# MCORD_AFE.net
KiCad netlist of a schematic drawn in Altium Designer
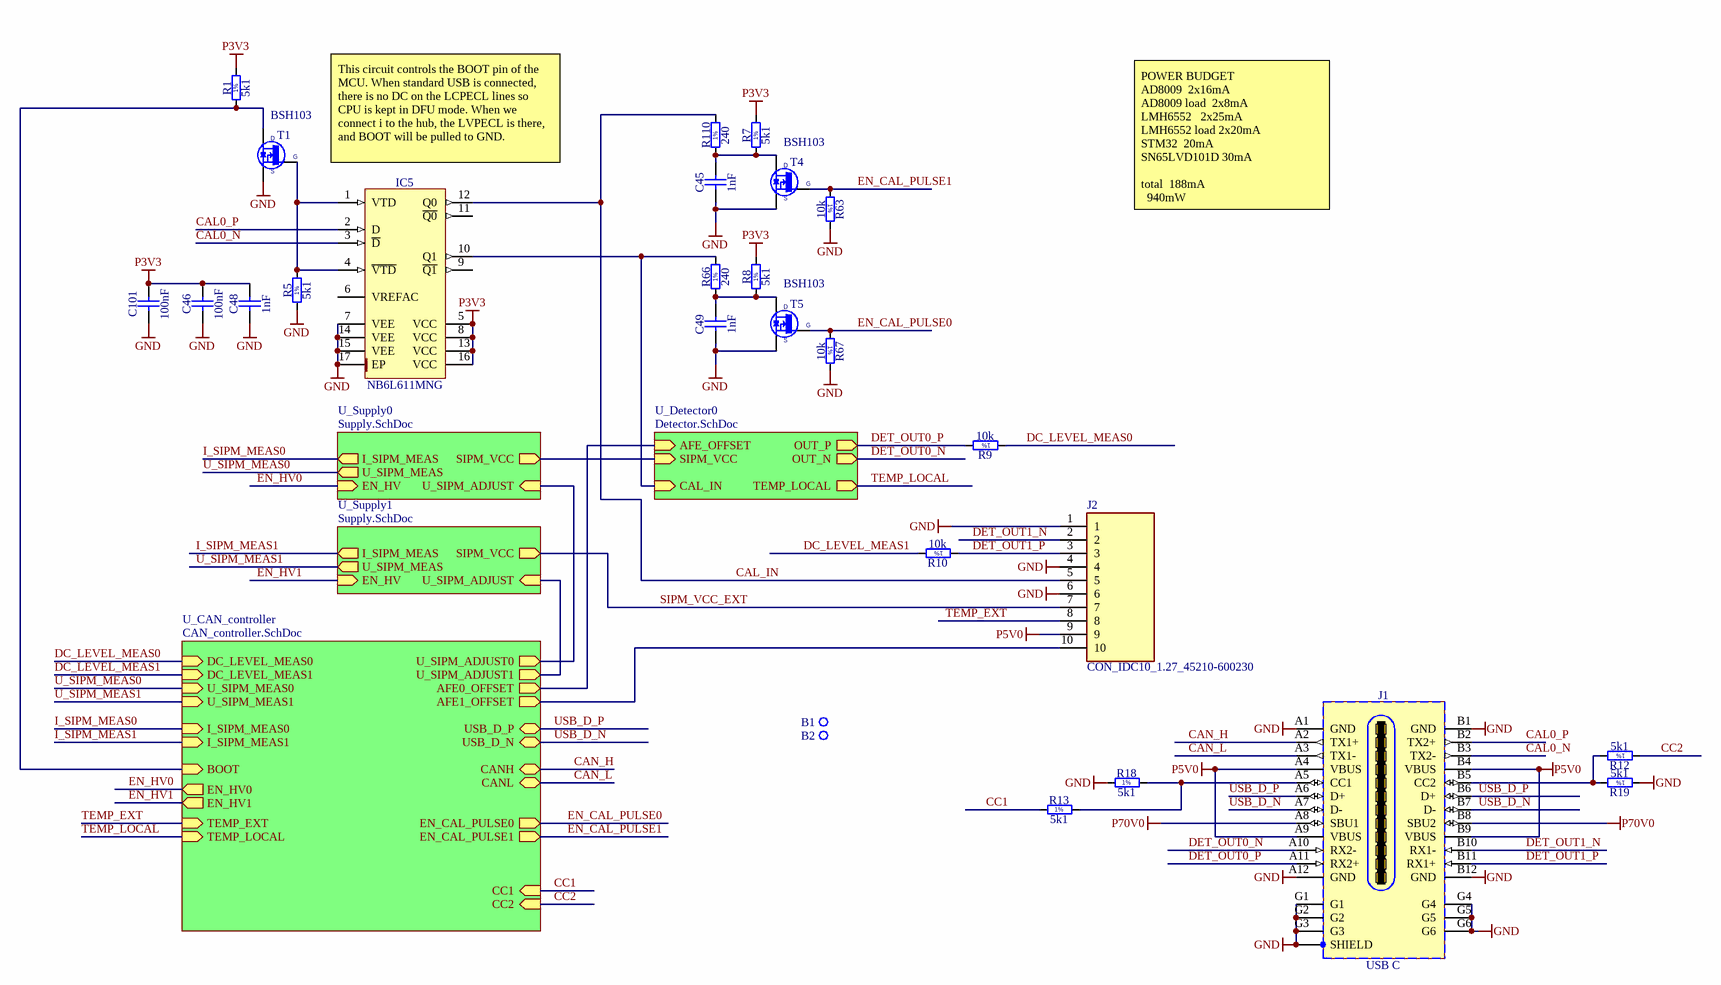
[diagram p0: MCORD_AFE.SchDoc]

(export (version "E")
  (design (tool "Eeschema 10.0.6"))
  (components
    (comp (ref "B1")
      (value "Plated Hole")
      (footprint "MTG320_550")
      (description "Single Terminal Socket")
      (fields (field (name "PART NUMBER") "PLATED_HOLE3.2_PAD5.5") (field (name "AUTHOR") "CERN DEM JMW"))
      (libsource (lib "Eletro-mechanical") (part "Single Terminal Socket"))
    )
    (comp (ref "B2")
      (value "Plated Hole")
      (footprint "MTG320_550")
      (description "Single Terminal Socket")
      (fields (field (name "PART NUMBER") "PLATED_HOLE3.2_PAD5.5") (field (name "AUTHOR") "CERN DEM JMW"))
      (libsource (lib "Eletro-mechanical") (part "Single Terminal Socket"))
    )
    (comp (ref "C45")
      (value "1nF")
      (footprint "CAPC1005X55N")
      (description "Non-polarised capacitor")
      (fields
        (field (name "PART NUMBER") "CC0402_1NF_50V_5%_C0G")
        (field (name "VOLTAGE") "50V")
        (field (name "AUTHOR") "CERN DEM BC")
      )
      (libsource (lib "Capacitors") (part "Capacitor - non polarized"))
    )
    (comp (ref "C46")
      (value "100nF")
      (footprint "CAPC1005X55N")
      (description "Non-polarised capacitor")
      (fields
        (field (name "PART NUMBER") "CC0402_100NF_16V_10%_X7R")
        (field (name "VOLTAGE") "16V")
        (field (name "AUTHOR") "CERN DEM JLC")
      )
      (libsource (lib "Capacitors") (part "Capacitor - non polarized"))
    )
    (comp (ref "C48")
      (value "1nF")
      (footprint "CAPC1005X55N")
      (description "Non-polarised capacitor")
      (fields
        (field (name "PART NUMBER") "CC0402_1NF_50V_5%_C0G")
        (field (name "VOLTAGE") "50V")
        (field (name "AUTHOR") "CERN DEM BC")
      )
      (libsource (lib "Capacitors") (part "Capacitor - non polarized"))
    )
    (comp (ref "C49")
      (value "1nF")
      (footprint "CAPC1005X55N")
      (description "Non-polarised capacitor")
      (fields
        (field (name "PART NUMBER") "CC0402_1NF_50V_5%_C0G")
        (field (name "VOLTAGE") "50V")
        (field (name "AUTHOR") "CERN DEM BC")
      )
      (libsource (lib "Capacitors") (part "Capacitor - non polarized"))
    )
    (comp (ref "C101")
      (value "100nF")
      (footprint "CAPC1005X55N")
      (description "Non-polarised capacitor")
      (fields
        (field (name "PART NUMBER") "CC0402_100NF_16V_10%_X7R")
        (field (name "VOLTAGE") "16V")
        (field (name "AUTHOR") "CERN DEM JLC")
      )
      (libsource (lib "Capacitors") (part "Capacitor - non polarized"))
    )
    (comp (ref "IC5")
      (value "NB6L611MNG")
      (footprint "QFN50P300X300X100-17N-S185")
      (description "2.5V/3.3V 1:2 Differential LVPECL Clock / Data Fanout Buffer")
      (fields (field (name "MANUFACTURER") "ON SEMICONDUCTOR") (field (name "AUTHOR") "CERN DEM JLC"))
      (libsource (lib "ICs And Semiconductors") (part "NB6L611MNG"))
    )
    (comp (ref "J1")
      (value "USB C")
      (footprint "AMPHENOL_MUSBRM5C1M0")
      (description "2x12 Pin + 6G + 1 Shield  USB Type C Receptacle")
      (fields
        (field (name "PART NUMBER") "AMPHENOL_MUSBRM5C1M0")
        (field (name "MANUFACTURER") "AMPHENOL")
        (field (name "AUTHOR") "CERN DEM BC")
      )
      (libsource (lib "Connectors") (part "Connector USB C 24 Pin + 6G +1 Shield"))
    )
    (comp (ref "J2")
      (value "CON_IDC10_1.27_45210-600230")
      (footprint "SamacSys:SHDR10W38P127_2X5_1069X594X747P")
      (description "Connector")
      (fields
        (field (name "MANUFACTURER_PART_NUMBER") "45210-600230")
        (field (name "MOUSER PART NUMBER") "517-45210-600230")
      )
      (libsource (lib "LIBRARY_SCH") (part "CON_IDC10_1.27_45210-600230"))
    )
    (comp (ref "R1")
      (value "5k1")
      (footprint "RESC1005X40N")
      (description "Resistor - 1%")
      (fields
        (field (name "PART NUMBER") "R0402_5K1_1%_0.0625W_100PPM")
        (field (name "POWER") "0.0625W")
        (field (name "AUTHOR") "CERN DEM JLC")
      )
      (libsource (lib "Resistors") (part "Resistor - 1%"))
    )
    (comp (ref "R5")
      (value "5k1")
      (footprint "RESC1005X40N")
      (description "Resistor - 1%")
      (fields
        (field (name "PART NUMBER") "R0402_5K1_1%_0.0625W_100PPM")
        (field (name "POWER") "0.0625W")
        (field (name "AUTHOR") "CERN DEM JLC")
      )
      (libsource (lib "Resistors") (part "Resistor - 1%"))
    )
    (comp (ref "R7")
      (value "5k1")
      (footprint "RESC1005X40N")
      (description "Resistor - 1%")
      (fields
        (field (name "PART NUMBER") "R0402_5K1_1%_0.0625W_100PPM")
        (field (name "POWER") "0.0625W")
        (field (name "AUTHOR") "CERN DEM JLC")
      )
      (libsource (lib "Resistors") (part "Resistor - 1%"))
    )
    (comp (ref "R8")
      (value "5k1")
      (footprint "RESC1005X40N")
      (description "Resistor - 1%")
      (fields
        (field (name "PART NUMBER") "R0402_5K1_1%_0.0625W_100PPM")
        (field (name "POWER") "0.0625W")
        (field (name "AUTHOR") "CERN DEM JLC")
      )
      (libsource (lib "Resistors") (part "Resistor - 1%"))
    )
    (comp (ref "R9")
      (value "10k")
      (footprint "RESC1005X40N")
      (description "Resistor - 1%")
      (fields
        (field (name "PART NUMBER") "R0402_10K_1%_0.0625W_100PPM")
        (field (name "POWER") "0.0625W")
        (field (name "AUTHOR") "CERN DEM JLC")
      )
      (libsource (lib "Resistors") (part "Resistor - 1%"))
    )
    (comp (ref "R10")
      (value "10k")
      (footprint "RESC1005X40N")
      (description "Resistor - 1%")
      (fields
        (field (name "PART NUMBER") "R0402_10K_1%_0.0625W_100PPM")
        (field (name "POWER") "0.0625W")
        (field (name "AUTHOR") "CERN DEM JLC")
      )
      (libsource (lib "Resistors") (part "Resistor - 1%"))
    )
    (comp (ref "R12")
      (value "5k1")
      (footprint "RESC1005X40N")
      (description "Resistor - 1%")
      (fields
        (field (name "PART NUMBER") "R0402_5K1_1%_0.0625W_100PPM")
        (field (name "POWER") "0.0625W")
        (field (name "AUTHOR") "CERN DEM JLC")
      )
      (libsource (lib "Resistors") (part "Resistor - 1%"))
    )
    (comp (ref "R13")
      (value "5k1")
      (footprint "RESC1005X40N")
      (description "Resistor - 1%")
      (fields
        (field (name "PART NUMBER") "R0402_5K1_1%_0.0625W_100PPM")
        (field (name "POWER") "0.0625W")
        (field (name "AUTHOR") "CERN DEM JLC")
      )
      (libsource (lib "Resistors") (part "Resistor - 1%"))
    )
    (comp (ref "R18")
      (value "5k1")
      (footprint "RESC1005X40N")
      (description "Resistor - 1%")
      (fields
        (field (name "PART NUMBER") "R0402_5K1_1%_0.0625W_100PPM")
        (field (name "POWER") "0.0625W")
        (field (name "AUTHOR") "CERN DEM JLC")
      )
      (libsource (lib "Resistors") (part "Resistor - 1%"))
    )
    (comp (ref "R19")
      (value "5k1")
      (footprint "RESC1005X40N")
      (description "Resistor - 1%")
      (fields
        (field (name "PART NUMBER") "R0402_5K1_1%_0.0625W_100PPM")
        (field (name "POWER") "0.0625W")
        (field (name "AUTHOR") "CERN DEM JLC")
      )
      (libsource (lib "Resistors") (part "Resistor - 1%"))
    )
    (comp (ref "R63")
      (value "10k")
      (footprint "RESC1005X40N")
      (description "Resistor - 1%")
      (fields
        (field (name "PART NUMBER") "R0402_10K_1%_0.0625W_100PPM")
        (field (name "POWER") "0.0625W")
        (field (name "AUTHOR") "CERN DEM JLC")
      )
      (libsource (lib "Resistors") (part "Resistor - 1%"))
    )
    (comp (ref "R66")
      (value "240")
      (footprint "RESC1005X40N")
      (description "Resistor - 1%")
      (fields
        (field (name "PART NUMBER") "R0402_240R_1%_0.0625W_100PPM")
        (field (name "POWER") "0.0625W")
        (field (name "AUTHOR") "CERN DEM JLC")
      )
      (libsource (lib "Resistors") (part "Resistor - 1%"))
    )
    (comp (ref "R67")
      (value "10k")
      (footprint "RESC1005X40N")
      (description "Resistor - 1%")
      (fields
        (field (name "PART NUMBER") "R0402_10K_1%_0.0625W_100PPM")
        (field (name "POWER") "0.0625W")
        (field (name "AUTHOR") "CERN DEM JLC")
      )
      (libsource (lib "Resistors") (part "Resistor - 1%"))
    )
    (comp (ref "R110")
      (value "240")
      (footprint "RESC1005X40N")
      (description "Resistor - 1%")
      (fields
        (field (name "PART NUMBER") "R0402_240R_1%_0.0625W_100PPM")
        (field (name "POWER") "0.0625W")
        (field (name "AUTHOR") "CERN DEM JLC")
      )
      (libsource (lib "Resistors") (part "Resistor - 1%"))
    )
    (comp (ref "T1")
      (value "BSH103")
      (footprint "SOT95P230X110-3N")
      (description "N-CHANNEL MOSFET WITH DIODE")
      (fields (field (name "MANUFACTURER") "NEXPERIA") (field (name "AUTHOR") "CERN DEM JLC"))
      (libsource (lib "ICs And Semiconductors") (part "N-MOSFET-D 1G 2S 3D"))
    )
    (comp (ref "T4")
      (value "BSH103")
      (footprint "SOT95P230X110-3N")
      (description "N-CHANNEL MOSFET WITH DIODE")
      (fields (field (name "MANUFACTURER") "NEXPERIA") (field (name "AUTHOR") "CERN DEM JLC"))
      (libsource (lib "ICs And Semiconductors") (part "N-MOSFET-D 1G 2S 3D"))
    )
    (comp (ref "T5")
      (value "BSH103")
      (footprint "SOT95P230X110-3N")
      (description "N-CHANNEL MOSFET WITH DIODE")
      (fields (field (name "MANUFACTURER") "NEXPERIA") (field (name "AUTHOR") "CERN DEM JLC"))
      (libsource (lib "ICs And Semiconductors") (part "N-MOSFET-D 1G 2S 3D"))
    )
  )
  (nets
    (net (code "2") (name "/AFE1_OFFSET") (class "Default")
      (node (ref "J2") (pin "10") (pinfunction "10_10") (pintype "passive"))
    )
    (net (code "3") (name "/BOOT") (class "Default")
      (node (ref "R1") (pin "1") (pinfunction "1_1") (pintype "passive"))
      (node (ref "T1") (pin "3") (pinfunction "D_3") (pintype "passive"))
    )
    (net (code "4") (name "/CAL0_N") (class "Default")
      (node (ref "IC5") (pin "3") (pinfunction "~{D}_3") (pintype "input"))
      (node (ref "J1") (pin "B3") (pinfunction "TX2-_B3") (pintype "output"))
    )
    (net (code "5") (name "/CAL0_P") (class "Default")
      (node (ref "IC5") (pin "2") (pinfunction "D_2") (pintype "input"))
      (node (ref "J1") (pin "B2") (pinfunction "TX2+_B2") (pintype "output"))
    )
    (net (code "6") (name "/CAL_IN") (class "Default")
      (node (ref "IC5") (pin "12") (pinfunction "Q0_12") (pintype "output"))
      (node (ref "J2") (pin "5") (pinfunction "5_5") (pintype "passive"))
      (node (ref "R110") (pin "2") (pinfunction "2_2") (pintype "passive"))
    )
    (net (code "7") (name "/CAL_IN_1") (class "Default")
      (node (ref "IC5") (pin "10") (pinfunction "Q1_10") (pintype "output"))
      (node (ref "R66") (pin "2") (pinfunction "2_2") (pintype "passive"))
    )
    (net (code "8") (name "/CAN_H") (class "Default")
      (node (ref "J1") (pin "A2") (pinfunction "TX1+_A2") (pintype "output"))
    )
    (net (code "9") (name "/CAN_L") (class "Default")
      (node (ref "J1") (pin "A3") (pinfunction "TX1-_A3") (pintype "output"))
    )
    (net (code "10") (name "/CC1") (class "Default")
      (node (ref "R13") (pin "1") (pinfunction "1_1") (pintype "passive"))
    )
    (net (code "11") (name "/CC2") (class "Default")
      (node (ref "R12") (pin "1") (pinfunction "1_1") (pintype "passive"))
    )
    (net (code "12") (name "/DC_LEVEL_MEAS0") (class "Default")
      (node (ref "R9") (pin "1") (pinfunction "1_1") (pintype "passive"))
    )
    (net (code "13") (name "/DC_LEVEL_MEAS1") (class "Default")
      (node (ref "R10") (pin "2") (pinfunction "2_2") (pintype "passive"))
    )
    (net (code "14") (name "/DET_OUT0_N") (class "Default")
      (node (ref "J1") (pin "A10") (pinfunction "RX2-_A10") (pintype "input"))
    )
    (net (code "15") (name "/DET_OUT0_P") (class "Default")
      (node (ref "J1") (pin "A11") (pinfunction "RX2+_A11") (pintype "input"))
      (node (ref "R9") (pin "2") (pinfunction "2_2") (pintype "passive"))
    )
    (net (code "16") (name "/DET_OUT1_N") (class "Default")
      (node (ref "J1") (pin "B10") (pinfunction "RX1-_B10") (pintype "input"))
      (node (ref "J2") (pin "2") (pinfunction "2_2") (pintype "passive"))
    )
    (net (code "17") (name "/DET_OUT1_P") (class "Default")
      (node (ref "J1") (pin "B11") (pinfunction "RX1+_B11") (pintype "input"))
      (node (ref "J2") (pin "3") (pinfunction "3_3") (pintype "passive"))
      (node (ref "R10") (pin "1") (pinfunction "1_1") (pintype "passive"))
    )
    (net (code "18") (name "/EN_CAL_PULSE0") (class "Default")
      (node (ref "R67") (pin "1") (pinfunction "1_1") (pintype "passive"))
      (node (ref "T5") (pin "1") (pinfunction "G_1") (pintype "passive"))
    )
    (net (code "19") (name "/EN_CAL_PULSE1") (class "Default")
      (node (ref "R63") (pin "1") (pinfunction "1_1") (pintype "passive"))
      (node (ref "T4") (pin "1") (pinfunction "G_1") (pintype "passive"))
    )
    (net (code "25") (name "/SIPM_VCC_EXT") (class "Default")
      (node (ref "J2") (pin "7") (pinfunction "7_7") (pintype "passive"))
    )
    (net (code "26") (name "/TEMP_EXT") (class "Default")
      (node (ref "J2") (pin "8") (pinfunction "8_8") (pintype "passive"))
    )
    (net (code "28") (name "/USB_D_N") (class "Default")
      (node (ref "J1") (pin "A7") (pinfunction "D-_A7") (pintype "bidirectional"))
      (node (ref "J1") (pin "B7") (pinfunction "D-_B7") (pintype "bidirectional"))
    )
    (net (code "29") (name "/USB_D_P") (class "Default")
      (node (ref "J1") (pin "A6") (pinfunction "D+_A6") (pintype "bidirectional"))
      (node (ref "J1") (pin "B6") (pinfunction "D+_B6") (pintype "bidirectional"))
    )
    (net (code "34") (name "GND") (class "Default")
      (node (ref "C101") (pin "1") (pinfunction "1_1") (pintype "passive"))
      (node (ref "C45") (pin "1") (pinfunction "1_1") (pintype "passive"))
      (node (ref "C46") (pin "1") (pinfunction "1_1") (pintype "passive"))
      (node (ref "C48") (pin "1") (pinfunction "1_1") (pintype "passive"))
      (node (ref "C49") (pin "1") (pinfunction "1_1") (pintype "passive"))
      (node (ref "IC5") (pin "14") (pinfunction "VEE_14") (pintype "power_in"))
      (node (ref "IC5") (pin "15") (pinfunction "VEE_15") (pintype "power_in"))
      (node (ref "IC5") (pin "17") (pinfunction "EP_17") (pintype "power_in"))
      (node (ref "IC5") (pin "7") (pinfunction "VEE_7") (pintype "power_in"))
      (node (ref "J1") (pin "A1") (pinfunction "GND_A1") (pintype "power_in"))
      (node (ref "J1") (pin "A12") (pinfunction "GND_A12") (pintype "power_in"))
      (node (ref "J1") (pin "B1") (pinfunction "GND_B1") (pintype "power_in"))
      (node (ref "J1") (pin "B12") (pinfunction "GND_B12") (pintype "power_in"))
      (node (ref "J1") (pin "G1") (pinfunction "G1_G1") (pintype "power_in"))
      (node (ref "J1") (pin "G2") (pinfunction "G2_G2") (pintype "power_in"))
      (node (ref "J1") (pin "G3") (pinfunction "G3_G3") (pintype "power_in"))
      (node (ref "J1") (pin "G4") (pinfunction "G4_G4") (pintype "power_in"))
      (node (ref "J1") (pin "G5") (pinfunction "G5_G5") (pintype "power_in"))
      (node (ref "J1") (pin "G6") (pinfunction "G6_G6") (pintype "power_in"))
      (node (ref "J1") (pin "SHIELD") (pinfunction "SHIELD_SHIELD") (pintype "power_in"))
      (node (ref "J2") (pin "1") (pinfunction "1_1") (pintype "passive"))
      (node (ref "J2") (pin "4") (pinfunction "4_4") (pintype "passive"))
      (node (ref "J2") (pin "6") (pinfunction "6_6") (pintype "passive"))
      (node (ref "R18") (pin "1") (pinfunction "1_1") (pintype "passive"))
      (node (ref "R19") (pin "1") (pinfunction "1_1") (pintype "passive"))
      (node (ref "R5") (pin "1") (pinfunction "1_1") (pintype "passive"))
      (node (ref "R63") (pin "2") (pinfunction "2_2") (pintype "passive"))
      (node (ref "R67") (pin "2") (pinfunction "2_2") (pintype "passive"))
      (node (ref "T1") (pin "2") (pinfunction "S_2") (pintype "passive"))
      (node (ref "T4") (pin "2") (pinfunction "S_2") (pintype "passive"))
      (node (ref "T5") (pin "2") (pinfunction "S_2") (pintype "passive"))
    )
    (net (code "35") (name "Net-(IC5-VTD)") (class "Default")
      (node (ref "IC5") (pin "1") (pinfunction "VTD_1") (pintype "input"))
      (node (ref "IC5") (pin "4") (pinfunction "~{VTD}_4") (pintype "input"))
      (node (ref "R5") (pin "2") (pinfunction "2_2") (pintype "passive"))
      (node (ref "T1") (pin "1") (pinfunction "G_1") (pintype "passive"))
    )
    (net (code "36") (name "Net-(J1-CC1)") (class "Default")
      (node (ref "J1") (pin "A5") (pinfunction "CC1_A5") (pintype "bidirectional"))
      (node (ref "R13") (pin "2") (pinfunction "2_2") (pintype "passive"))
      (node (ref "R18") (pin "2") (pinfunction "2_2") (pintype "passive"))
    )
    (net (code "37") (name "Net-(J1-CC2)") (class "Default")
      (node (ref "J1") (pin "B5") (pinfunction "CC2_B5") (pintype "bidirectional"))
      (node (ref "R12") (pin "2") (pinfunction "2_2") (pintype "passive"))
      (node (ref "R19") (pin "2") (pinfunction "2_2") (pintype "passive"))
    )
    (net (code "38") (name "Net-(T4-D)") (class "Default")
      (node (ref "C45") (pin "2") (pinfunction "2_2") (pintype "passive"))
      (node (ref "R110") (pin "1") (pinfunction "1_1") (pintype "passive"))
      (node (ref "R7") (pin "1") (pinfunction "1_1") (pintype "passive"))
      (node (ref "T4") (pin "3") (pinfunction "D_3") (pintype "passive"))
    )
    (net (code "39") (name "Net-(T5-D)") (class "Default")
      (node (ref "C49") (pin "2") (pinfunction "2_2") (pintype "passive"))
      (node (ref "R66") (pin "1") (pinfunction "1_1") (pintype "passive"))
      (node (ref "R8") (pin "1") (pinfunction "1_1") (pintype "passive"))
      (node (ref "T5") (pin "3") (pinfunction "D_3") (pintype "passive"))
    )
    (net (code "40") (name "P3V3") (class "Default")
      (node (ref "C101") (pin "2") (pinfunction "2_2") (pintype "passive"))
      (node (ref "C46") (pin "2") (pinfunction "2_2") (pintype "passive"))
      (node (ref "C48") (pin "2") (pinfunction "2_2") (pintype "passive"))
      (node (ref "IC5") (pin "13") (pinfunction "VCC_13") (pintype "power_in"))
      (node (ref "IC5") (pin "16") (pinfunction "VCC_16") (pintype "power_in"))
      (node (ref "IC5") (pin "5") (pinfunction "VCC_5") (pintype "power_in"))
      (node (ref "IC5") (pin "8") (pinfunction "VCC_8") (pintype "power_in"))
      (node (ref "R1") (pin "2") (pinfunction "2_2") (pintype "passive"))
      (node (ref "R7") (pin "2") (pinfunction "2_2") (pintype "passive"))
      (node (ref "R8") (pin "2") (pinfunction "2_2") (pintype "passive"))
    )
    (net (code "41") (name "P5V0") (class "Default")
      (node (ref "J1") (pin "A4") (pinfunction "VBUS_A4") (pintype "power_in"))
      (node (ref "J1") (pin "A9") (pinfunction "VBUS_A9") (pintype "power_in"))
      (node (ref "J1") (pin "B4") (pinfunction "VBUS_B4") (pintype "power_in"))
      (node (ref "J1") (pin "B9") (pinfunction "VBUS_B9") (pintype "power_in"))
      (node (ref "J2") (pin "9") (pinfunction "9_9") (pintype "passive"))
    )
    (net (code "42") (name "P70V0") (class "Default")
      (node (ref "J1") (pin "A8") (pinfunction "SBU1_A8") (pintype "bidirectional"))
      (node (ref "J1") (pin "B8") (pinfunction "SBU2_B8") (pintype "bidirectional"))
    )
    (net (code "43") (name "unconnected-(B1-Pad1)") (class "Default")
      (node (ref "B1") (pin "1") (pinfunction "1_1") (pintype "bidirectional"))
    )
    (net (code "44") (name "unconnected-(B2-Pad1)") (class "Default")
      (node (ref "B2") (pin "1") (pinfunction "1_1") (pintype "bidirectional"))
    )
    (net (code "45") (name "unconnected-(IC5-VREFAC-Pad6)") (class "Default")
      (node (ref "IC5") (pin "6") (pinfunction "VREFAC_6") (pintype "passive"))
    )
    (net (code "46") (name "unconnected-(IC5-~{Q0}-Pad11)") (class "Default")
      (node (ref "IC5") (pin "11") (pinfunction "~{Q0}_11") (pintype "output"))
    )
    (net (code "47") (name "unconnected-(IC5-~{Q1}-Pad9)") (class "Default")
      (node (ref "IC5") (pin "9") (pinfunction "~{Q1}_9") (pintype "output"))
    )
  )
)
